# IO.net
KiCad netlist of a schematic drawn in Altium Designer
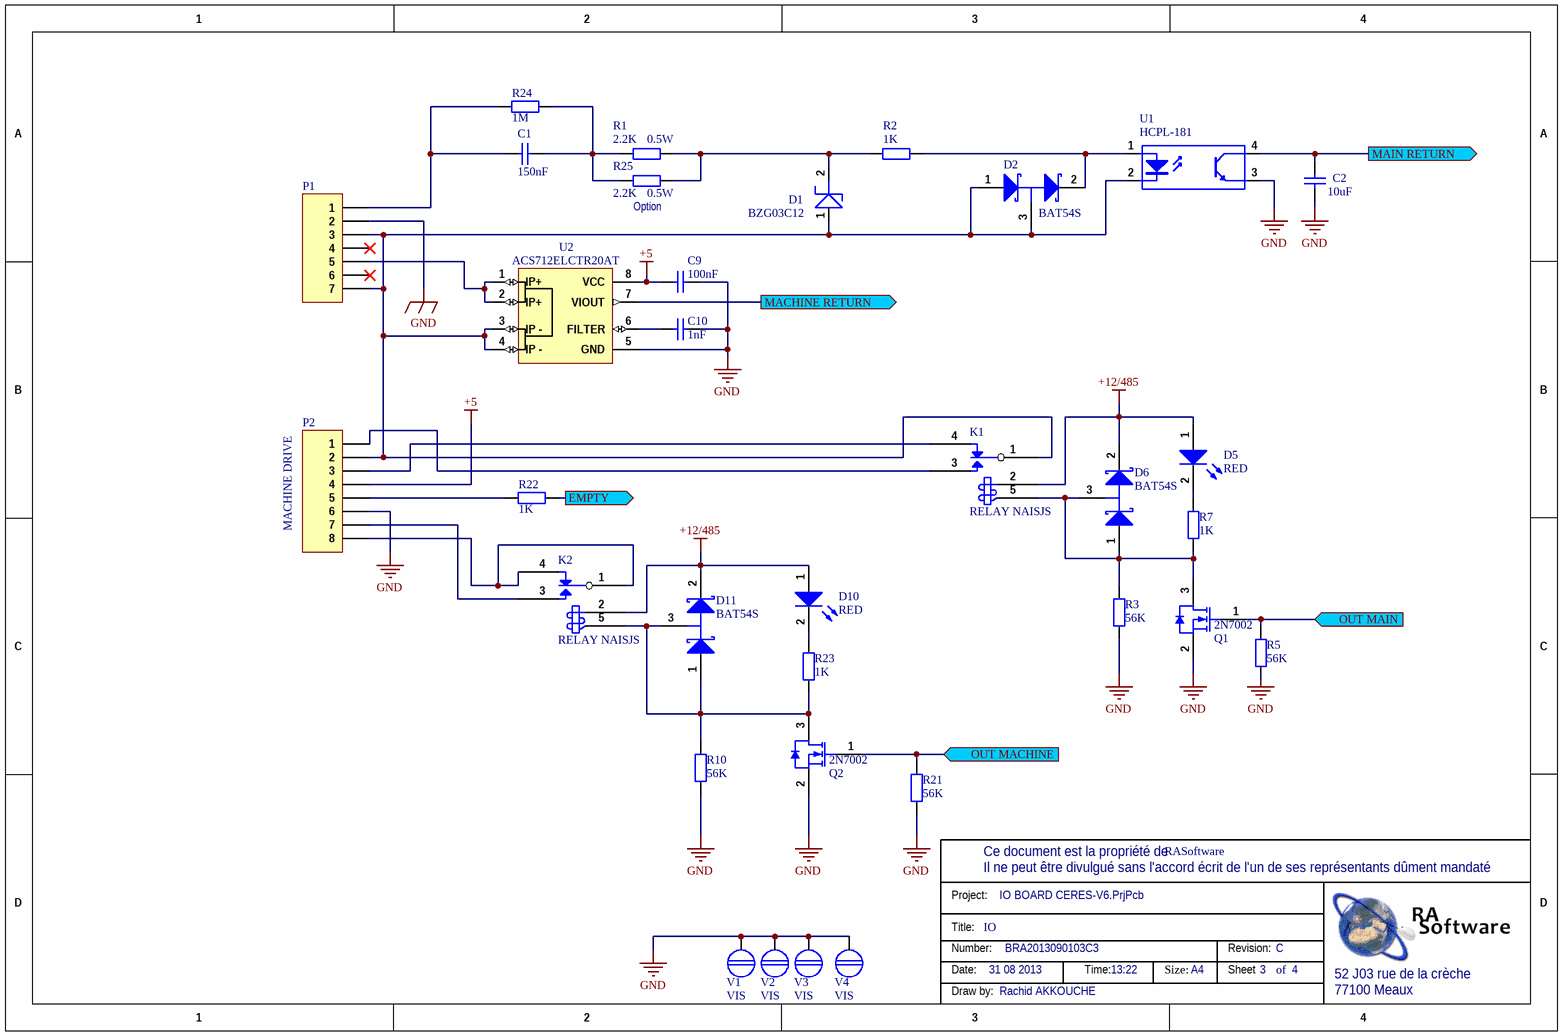
[diagram p0: IO.SchDoc]

(export (version "E")
  (design (tool "Eeschema 10.0.6"))
  (components
    (comp (ref "C1")
      (value "150nF")
      (footprint "C1210")
      (description "Capacitor")
      (fields
        (field (name "MANUFACTURER") "KEMET")
        (field (name "MANUFACTURER PART NUMBER") "C1210V154KCRACTU")
      )
      (libsource (lib "Miscellaneous Devices") (part "Cap"))
    )
    (comp (ref "C2")
      (value "10uF")
      (footprint "bra:C0805")
      (description "Capacitor")
      (fields
        (field (name "MANUFACTURER") "YAGEO")
        (field (name "MANUFACTURER PART NUMBER") "CC0805KKX5R5BB106")
      )
      (libsource (lib "BRA") (part "Cap 0805 1uF"))
    )
    (comp (ref "C9")
      (value "100nF")
      (footprint "SYLANN:C0805")
      (description "Capacitor")
      (fields
        (field (name "MANUFACTURER") "MULTICOMP")
        (field (name "MANUFACTURER PART NUMBER") "MCCA000296")
      )
      (libsource (lib "BRA") (part "Cap 0805 100nF"))
    )
    (comp (ref "C10")
      (value "1nF")
      (footprint "SYLANN:C0805")
      (description "Capacitor")
      (fields
        (field (name "MANUFACTURER") "SAMSUNG")
        (field (name "MANUFACTURER PART NUMBER") "CL05B102KB5NNNC")
      )
      (libsource (lib "BRA") (part "Cap 0805 1nF"))
    )
    (comp (ref "D1")
      (value "BZG03C12")
      (footprint "sma")
      (fields (field (name "MANUFACTURER") "VISHAY") (field (name "MANUFACTURER PART NUMBER") "BZG03C12TR3"))
      (libsource (lib "UTIL_Library") (part "DZ"))
    )
    (comp (ref "D2")
      (value "BAT54S")
      (footprint "SOT23")
      (description "Schottky Barrier Double Diode")
      (fields (field (name "MANUFACTURER") "MULTICOMP"))
      (libsource (lib "Ares") (part "BAT54S"))
    )
    (comp (ref "D5")
      (value "HSMH-C190")
      (footprint "0603-LEDR")
      (description "Surface Mount Chip LED, Red")
      (fields
        (field (name "MANUFACTURER") "AVAGO TECHNOLOGIES")
        (field (name "MANUFACTURER PART NUMBER") "HSMH-C190.")
        (field (name "COULEUR") "RED")
        (field (name "LONGUEUR/HAUTEUR") "1.6")
      )
      (libsource (lib "BRA") (part "HSMH-C190"))
    )
    (comp (ref "D6")
      (value "BAT54S")
      (footprint "SOT23")
      (description "Schottky Barrier Double Diode")
      (fields (field (name "MANUFACTURER") "MULTICOMP"))
      (libsource (lib "Ares") (part "BAT54S"))
    )
    (comp (ref "D10")
      (value "HSMH-C190")
      (footprint "0603-LEDR")
      (description "Surface Mount Chip LED, Red")
      (fields
        (field (name "MANUFACTURER") "AVAGO TECHNOLOGIES")
        (field (name "MANUFACTURER PART NUMBER") "HSMH-C190.")
        (field (name "COULEUR") "RED")
        (field (name "LONGUEUR/HAUTEUR") "1.6")
      )
      (libsource (lib "BRA") (part "HSMH-C190"))
    )
    (comp (ref "D11")
      (value "BAT54S")
      (footprint "SOT23")
      (description "Schottky Barrier Double Diode")
      (fields (field (name "MANUFACTURER") "MULTICOMP"))
      (libsource (lib "Ares") (part "BAT54S"))
    )
    (comp (ref "K1")
      (value "RELAY NAISJS")
      (footprint "RELAIG5L")
      (fields
        (field (name "MANUFACTURER") "OMRON ELECTRONIC COMPONENTS")
        (field (name "MANUFACTURER PART NUMBER") "G5LA1A412DC")
        (field (name "HAUTEUR, DIMENSION EXTERNE") "15.8")
      )
      (libsource (lib "UTIL_Library") (part "RELAY NAISJS"))
    )
    (comp (ref "K2")
      (value "RELAY NAISJS")
      (footprint "RELAIG5L")
      (fields
        (field (name "MANUFACTURER") "OMRON ELECTRONIC COMPONENTS")
        (field (name "MANUFACTURER PART NUMBER") "G5LA1A412DC")
        (field (name "HAUTEUR, DIMENSION EXTERNE") "15.8")
      )
      (libsource (lib "UTIL_Library") (part "RELAY NAISJS"))
    )
    (comp (ref "P1")
      (value "Header 7")
      (footprint "CO7P508-90")
      (description "Header, 7-Pin")
      (fields
        (field (name "MANUFACTURER") "FCI")
        (field (name "MANUFACTURER PART NUMBER") "20020110-H071A01LF")
        (field (name "PUBLISHER") "Altium Limited")
      )
      (libsource (lib "Miscellaneous Connectors") (part "Header 7"))
    )
    (comp (ref "P2")
      (value "Header 8")
      (footprint "CO8P508 - 90°")
      (description "Header, 8-Pin")
      (fields
        (field (name "MANUFACTURER") "CAMDENBOSS")
        (field (name "MANUFACTURER PART NUMBER") "CTB9350/8AO")
        (field (name "PUBLISHER") "Altium Limited")
      )
      (libsource (lib "Miscellaneous Connectors") (part "Header 8"))
    )
    (comp (ref "Q1")
      (value "2N7002")
      (footprint "SOT23")
      (description "N-channel Enhancement Mode Field-effect Transistor")
      (fields (field (name "MANUFACTURER") "FAIRCHILD SEMICONDUCTOR"))
      (libsource (lib "BRA") (part "2N7002"))
    )
    (comp (ref "Q2")
      (value "2N7002")
      (footprint "SOT23")
      (description "N-channel Enhancement Mode Field-effect Transistor")
      (fields (field (name "MANUFACTURER") "FAIRCHILD SEMICONDUCTOR"))
      (libsource (lib "BRA") (part "2N7002"))
    )
    (comp (ref "R1")
      (value "2.2K")
      (footprint "1206")
      (description "Resistor 1/2W")
      (fields
        (field (name "MANUFACTURER") "ROYAL OHM")
        (field (name "MANUFACTURER PART NUMBER") "HP06W2F2201T5E")
        (field (name "POWER") "0.5W")
      )
      (libsource (lib "BRA") (part "Resistor 2.2K 1/2W"))
    )
    (comp (ref "R2")
      (value "1K")
      (footprint "R0805")
      (description "Resistor")
      (fields
        (field (name "MANUFACTURER") "MULTICOMP")
        (field (name "MANUFACTURER PART NUMBER") "MC0.1W08051%1KFR")
      )
      (libsource (lib "Miscellaneous Devices") (part "Res2"))
    )
    (comp (ref "R3")
      (value "56K")
      (footprint "R0805")
      (description "Resistor")
      (fields
        (field (name "MANUFACTURER") "MULTICOMP")
        (field (name "MANUFACTURER PART NUMBER") "MC0.1W08051%56KFR")
      )
      (libsource (lib "BRA") (part "Resistor 0805 56K"))
    )
    (comp (ref "R5")
      (value "56K")
      (footprint "R0805")
      (description "Resistor")
      (fields
        (field (name "MANUFACTURER") "MULTICOMP")
        (field (name "MANUFACTURER PART NUMBER") "MC0.1W08051%56KFR")
      )
      (libsource (lib "BRA") (part "Resistor 0805 56K"))
    )
    (comp (ref "R7")
      (value "1K")
      (footprint "R0805")
      (description "Resistor")
      (fields
        (field (name "MANUFACTURER") "MULTICOMP")
        (field (name "MANUFACTURER PART NUMBER") "MC0.1W08051%1KFR")
      )
      (libsource (lib "BRA") (part "Resistor 0805 1K"))
    )
    (comp (ref "R10")
      (value "56K")
      (footprint "R0805")
      (description "Resistor")
      (fields
        (field (name "MANUFACTURER") "MULTICOMP")
        (field (name "MANUFACTURER PART NUMBER") "MC0.1W08051%56KFR")
      )
      (libsource (lib "BRA") (part "Resistor 0805 56K"))
    )
    (comp (ref "R21")
      (value "56K")
      (footprint "R0805")
      (description "Resistor")
      (fields
        (field (name "MANUFACTURER") "MULTICOMP")
        (field (name "MANUFACTURER PART NUMBER") "MC0.1W08051%56KFR")
      )
      (libsource (lib "BRA") (part "Resistor 0805 56K"))
    )
    (comp (ref "R22")
      (value "1K")
      (footprint "R0805")
      (description "Resistor")
      (fields
        (field (name "MANUFACTURER") "MULTICOMP")
        (field (name "MANUFACTURER PART NUMBER") "MC0.1W08051%1KFR")
      )
      (libsource (lib "") (part "Resistor 0805 1K_1"))
    )
    (comp (ref "R23")
      (value "1K")
      (footprint "R0805")
      (description "Resistor")
      (fields
        (field (name "MANUFACTURER") "MULTICOMP")
        (field (name "MANUFACTURER PART NUMBER") "MC0.1W08051%1KFR")
      )
      (libsource (lib "BRA") (part "Resistor 0805 1K"))
    )
    (comp (ref "R24")
      (value "1M")
      (footprint "R1206")
      (description "Resistor")
      (fields
        (field (name "MANUFACTURER") "Multicomp")
        (field (name "MANUFACTURER PART NUMBER") "MCHP06W2F1004T5E")
      )
      (libsource (lib "BRA") (part "Resistor 1206 1M"))
    )
    (comp (ref "R25")
      (value "2.2K")
      (footprint "1206")
      (description "Resistor 1/2W")
      (fields
        (field (name "MANUFACTURER") "ROYAL OHM")
        (field (name "MANUFACTURER PART NUMBER") "HP06W2F2201T5E")
        (field (name "POWER") "0.5W")
      )
      (libsource (lib "BRA") (part "Resistor 2.2K 1/2W"))
    )
    (comp (ref "U1")
      (value "HCPL-181")
      (footprint "OPTO-4PIN")
      (description "4-Pin Phototransistor Optocoupler")
      (fields
        (field (name "MANUFACTURER") "AVAGO TECHNOLOGIES")
        (field (name "MANUFACTURER PART NUMBER") "HCPL-181-00AE")
      )
      (libsource (lib "Miscellaneous Devices") (part "Optoisolator1"))
    )
    (comp (ref "U2")
      (value "ACS712")
      (footprint "SOIC8")
      (description "HALL EFFECT CURRENT SENSOR")
      (fields
        (field (name "MANUFACTURER") "ALLEGRO MICROSYSTEMS")
        (field (name "MANUFACTURER PART NUMBER") "ACS712ELCTR-20A-T")
        (field (name "SUPPLIER PART NUMBER 1") "ACS712ELCTR20AT")
      )
      (libsource (lib "BRA") (part "ACS712"))
    )
    (comp (ref "V1") (value "VIS") (footprint "vis42") (libsource (lib "UTIL_Library") (part "VIS")))
    (comp (ref "V2") (value "VIS") (footprint "vis42") (libsource (lib "UTIL_Library") (part "VIS")))
    (comp (ref "V3") (value "VIS") (footprint "vis42") (libsource (lib "UTIL_Library") (part "VIS")))
    (comp (ref "V4") (value "VIS") (footprint "vis42") (libsource (lib "UTIL_Library") (part "VIS")))
  )
  (nets
    (net (code "1") (name "+5") (class "Default")
      (node (ref "C9") (pin "2") (pinfunction "2_2") (pintype "passive"))
      (node (ref "P2") (pin "4") (pinfunction "4_4") (pintype "passive"))
      (node (ref "U2") (pin "8") (pinfunction "VCC_8") (pintype "power_in"))
    )
    (net (code "2") (name "+12{slash}485") (class "Default")
      (node (ref "D10") (pin "1") (pinfunction "A_1") (pintype "passive"))
      (node (ref "D11") (pin "2") (pinfunction "K_2") (pintype "passive"))
      (node (ref "D5") (pin "1") (pinfunction "A_1") (pintype "passive"))
      (node (ref "D6") (pin "2") (pinfunction "K_2") (pintype "passive"))
      (node (ref "K1") (pin "2") (pinfunction "COIL1_2") (pintype "passive"))
      (node (ref "K2") (pin "2") (pinfunction "COIL1_2") (pintype "passive"))
    )
    (net (code "3") (name "/EMPTY") (class "Default")
      (node (ref "R22") (pin "1") (pinfunction "1_1") (pintype "passive"))
    )
    (net (code "4") (name "/MACHINE RETURN") (class "Default")
      (node (ref "U2") (pin "7") (pinfunction "VIOUT_7") (pintype "output"))
    )
    (net (code "5") (name "/MAIN RETURN") (class "Default")
      (node (ref "C2") (pin "1") (pinfunction "1_1") (pintype "passive"))
      (node (ref "U1") (pin "4") (pinfunction "C_4") (pintype "passive"))
    )
    (net (code "6") (name "/OUT MACHINE") (class "Default")
      (node (ref "Q2") (pin "1") (pinfunction "G_1") (pintype "passive"))
      (node (ref "R21") (pin "2") (pinfunction "2_2") (pintype "passive"))
    )
    (net (code "7") (name "/OUT MAIN") (class "Default")
      (node (ref "Q1") (pin "1") (pinfunction "G_1") (pintype "passive"))
      (node (ref "R5") (pin "2") (pinfunction "2_2") (pintype "passive"))
    )
    (net (code "8") (name "GND") (class "Default")
      (node (ref "C10") (pin "2") (pinfunction "2_2") (pintype "passive"))
      (node (ref "C2") (pin "2") (pinfunction "2_2") (pintype "passive"))
      (node (ref "C9") (pin "1") (pinfunction "1_1") (pintype "passive"))
      (node (ref "P1") (pin "2") (pinfunction "2_2") (pintype "passive"))
      (node (ref "P2") (pin "6") (pinfunction "6_6") (pintype "passive"))
      (node (ref "Q1") (pin "2") (pinfunction "S_2") (pintype "passive"))
      (node (ref "Q2") (pin "2") (pinfunction "S_2") (pintype "passive"))
      (node (ref "R10") (pin "1") (pinfunction "1_1") (pintype "passive"))
      (node (ref "R21") (pin "1") (pinfunction "1_1") (pintype "passive"))
      (node (ref "R3") (pin "1") (pinfunction "1_1") (pintype "passive"))
      (node (ref "R5") (pin "1") (pinfunction "1_1") (pintype "passive"))
      (node (ref "U1") (pin "3") (pinfunction "E_3") (pintype "passive"))
      (node (ref "U2") (pin "5") (pinfunction "GND_5") (pintype "power_in"))
      (node (ref "V1") (pin "1") (pinfunction "1_1") (pintype "passive"))
      (node (ref "V2") (pin "1") (pinfunction "1_1") (pintype "passive"))
      (node (ref "V3") (pin "1") (pinfunction "1_1") (pintype "passive"))
      (node (ref "V4") (pin "1") (pinfunction "1_1") (pintype "passive"))
    )
    (net (code "9") (name "Net-(C1-Pad1)") (class "Default")
      (node (ref "C1") (pin "1") (pinfunction "1_1") (pintype "passive"))
      (node (ref "P1") (pin "1") (pinfunction "1_1") (pintype "passive"))
      (node (ref "R24") (pin "2") (pinfunction "2_2") (pintype "passive"))
    )
    (net (code "10") (name "Net-(C1-Pad2)") (class "Default")
      (node (ref "C1") (pin "2") (pinfunction "2_2") (pintype "passive"))
      (node (ref "R1") (pin "2") (pinfunction "2_2") (pintype "passive"))
      (node (ref "R24") (pin "1") (pinfunction "1_1") (pintype "passive"))
      (node (ref "R25") (pin "2") (pinfunction "2_2") (pintype "passive"))
    )
    (net (code "11") (name "Net-(D1-Pad2)") (class "Default")
      (node (ref "D1") (pin "2") (pinfunction "2_2") (pintype "passive"))
      (node (ref "R1") (pin "1") (pinfunction "1_1") (pintype "passive"))
      (node (ref "R2") (pin "1") (pinfunction "1_1") (pintype "passive"))
      (node (ref "R25") (pin "1") (pinfunction "1_1") (pintype "passive"))
    )
    (net (code "12") (name "Net-(D2-A)") (class "Default")
      (node (ref "D1") (pin "1") (pinfunction "1_1") (pintype "passive"))
      (node (ref "D2") (pin "1") (pinfunction "A_1") (pintype "passive"))
      (node (ref "D2") (pin "3") (pinfunction "C_3") (pintype "passive"))
      (node (ref "K1") (pin "1") (pinfunction "COMMON_1") (pintype "passive"))
      (node (ref "P1") (pin "3") (pinfunction "3_3") (pintype "passive"))
      (node (ref "P1") (pin "7") (pinfunction "7_7") (pintype "passive"))
      (node (ref "P2") (pin "2") (pinfunction "2_2") (pintype "passive"))
      (node (ref "U1") (pin "2") (pinfunction "K_2") (pintype "passive"))
      (node (ref "U2") (pin "3") (pinfunction "IP_-_3") (pintype "bidirectional"))
      (node (ref "U2") (pin "4") (pinfunction "IP_-_4") (pintype "bidirectional"))
    )
    (net (code "13") (name "Net-(D2-K)") (class "Default")
      (node (ref "D2") (pin "2") (pinfunction "K_2") (pintype "passive"))
      (node (ref "R2") (pin "2") (pinfunction "2_2") (pintype "passive"))
      (node (ref "U1") (pin "1") (pinfunction "A_1") (pintype "passive"))
    )
    (net (code "14") (name "Net-(D5-K)") (class "Default")
      (node (ref "D5") (pin "2") (pinfunction "K_2") (pintype "passive"))
      (node (ref "R7") (pin "2") (pinfunction "2_2") (pintype "passive"))
    )
    (net (code "15") (name "Net-(D6-A)") (class "Default")
      (node (ref "D6") (pin "1") (pinfunction "A_1") (pintype "passive"))
      (node (ref "D6") (pin "3") (pinfunction "C_3") (pintype "passive"))
      (node (ref "K1") (pin "5") (pinfunction "COIL2_5") (pintype "passive"))
      (node (ref "Q1") (pin "3") (pinfunction "D_3") (pintype "passive"))
      (node (ref "R3") (pin "2") (pinfunction "2_2") (pintype "passive"))
      (node (ref "R7") (pin "1") (pinfunction "1_1") (pintype "passive"))
    )
    (net (code "16") (name "Net-(D10-K)") (class "Default")
      (node (ref "D10") (pin "2") (pinfunction "K_2") (pintype "passive"))
      (node (ref "R23") (pin "2") (pinfunction "2_2") (pintype "passive"))
    )
    (net (code "17") (name "Net-(D11-A)") (class "Default")
      (node (ref "D11") (pin "1") (pinfunction "A_1") (pintype "passive"))
      (node (ref "D11") (pin "3") (pinfunction "C_3") (pintype "passive"))
      (node (ref "K2") (pin "5") (pinfunction "COIL2_5") (pintype "passive"))
      (node (ref "Q2") (pin "3") (pinfunction "D_3") (pintype "passive"))
      (node (ref "R10") (pin "2") (pinfunction "2_2") (pintype "passive"))
      (node (ref "R23") (pin "1") (pinfunction "1_1") (pintype "passive"))
    )
    (net (code "18") (name "Net-(K1-NC)") (class "Default")
      (node (ref "K1") (pin "4") (pinfunction "NC_4") (pintype "passive"))
      (node (ref "P2") (pin "3") (pinfunction "3_3") (pintype "passive"))
    )
    (net (code "19") (name "Net-(K1-NO)") (class "Default")
      (node (ref "K1") (pin "3") (pinfunction "NO_3") (pintype "passive"))
      (node (ref "P2") (pin "1") (pinfunction "1_1") (pintype "passive"))
    )
    (net (code "20") (name "Net-(K2-COMMON)") (class "Default")
      (node (ref "K2") (pin "1") (pinfunction "COMMON_1") (pintype "passive"))
      (node (ref "K2") (pin "4") (pinfunction "NC_4") (pintype "passive"))
      (node (ref "P2") (pin "8") (pinfunction "8_8") (pintype "passive"))
    )
    (net (code "21") (name "Net-(K2-NO)") (class "Default")
      (node (ref "K2") (pin "3") (pinfunction "NO_3") (pintype "passive"))
      (node (ref "P2") (pin "7") (pinfunction "7_7") (pintype "passive"))
    )
    (net (code "22") (name "Net-(P1-Pad5)") (class "Default")
      (node (ref "P1") (pin "5") (pinfunction "5_5") (pintype "passive"))
      (node (ref "U2") (pin "1") (pinfunction "IP+_1") (pintype "bidirectional"))
      (node (ref "U2") (pin "2") (pinfunction "IP+_2") (pintype "bidirectional"))
    )
    (net (code "23") (name "Net-(P2-Pad5)") (class "Default")
      (node (ref "P2") (pin "5") (pinfunction "5_5") (pintype "passive"))
      (node (ref "R22") (pin "2") (pinfunction "2_2") (pintype "passive"))
    )
    (net (code "24") (name "Net-(U2-FILTER)") (class "Default")
      (node (ref "C10") (pin "1") (pinfunction "1_1") (pintype "passive"))
      (node (ref "U2") (pin "6") (pinfunction "FILTER_6") (pintype "bidirectional"))
    )
    (net (code "25") (name "unconnected-(P1-Pad4)") (class "Default")
      (node (ref "P1") (pin "4") (pinfunction "4_4") (pintype "passive+no_connect"))
    )
    (net (code "26") (name "unconnected-(P1-Pad6)") (class "Default")
      (node (ref "P1") (pin "6") (pinfunction "6_6") (pintype "passive+no_connect"))
    )
  )
)
